# SWD_Adapter.net
KiCad netlist of a schematic drawn in Altium Designer
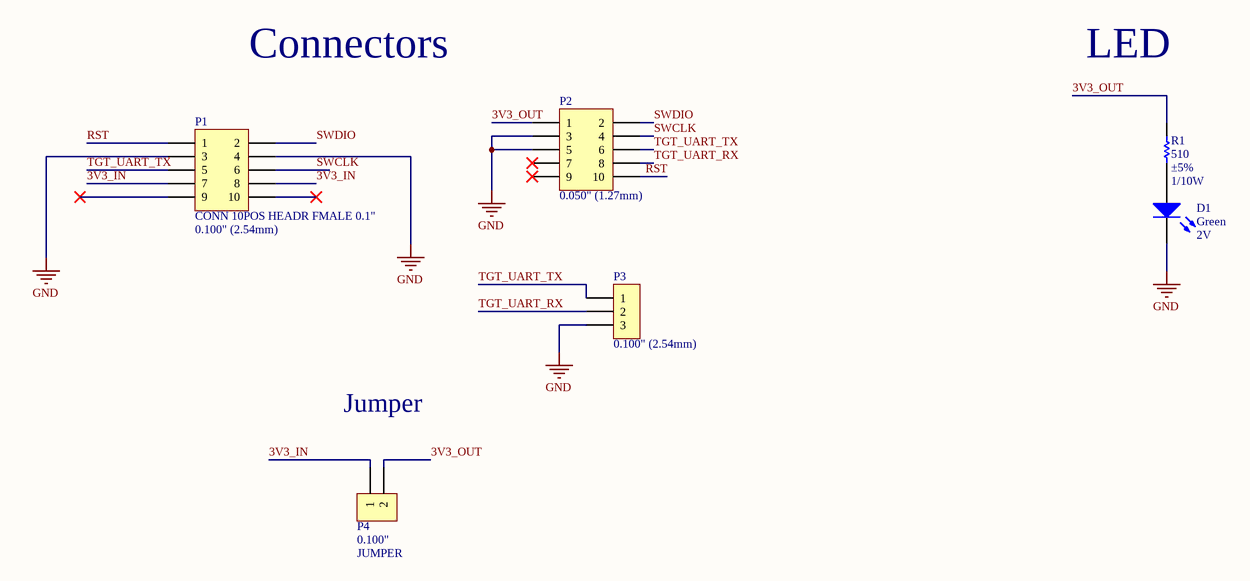
[diagram p0: SWD_Adapter.SchDoc]

(export (version "E")
  (design (tool "Eeschema 10.0.6"))
  (components
    (comp (ref "D1")
      (value "LED GREEN CLEAR 2V 0603")
      (footprint "LED_0603")
      (description "Green 572nm LED Indication - Discrete 2V 0603 (1608 Metric)")
      (fields
        (field (name "COLOR") "Green")
        (field (name "MANUFACTURER") "Wurth Electronics Inc.")
        (field (name "MANUFACTURER PART NUMBER") "150060VS75000")
        (field (name "VOLTAGE - FORWARD (VF) (TYP)") "2V")
      )
      (libsource (lib "Schematic Diagrams") (part "LED GREEN CLEAR 2V 0603"))
    )
    (comp (ref "P1")
      (value "CONN 10POS HEADR FMALE 0.1\"")
      (footprint "CONN ,10 POS Header 0.100\"")
      (description "10 Position Header Connector 0.100\" (2.54mm) Through Hole, Right Angle Gold")
      (fields (field (name "PITCH - MATING") "0.100\" (2.54mm)"))
      (libsource (lib "Schematic Diagrams") (part "CONN 10POS HEADR FMALE 0.1{dblquote}"))
    )
    (comp (ref "P2")
      (value "CONN 10POS HEADR MALE 0.05\"")
      (footprint "CONN, 10POS 0.05\" Debug Header")
      (description "10 Positions Header Connector 0.050\" (1.27mm) Surface Mount Gold")
      (fields (field (name "PITCH - MATING") "0.050\" (1.27mm)"))
      (libsource (lib "Schematic Diagrams") (part "CONN 10POS HEADR MALE 0.05{dblquote}"))
    )
    (comp (ref "P3")
      (value "CONN 3POS HEADR MALE 0.1\"")
      (description "3 Positions Header Connector 0.100\" (2.54mm) Through Hole Gold")
      (fields (field (name "VOLTAGE") "250V") (field (name "PITCH - MATING") "0.100\" (2.54mm)"))
      (libsource (lib "Schematic Diagrams") (part "CONN 3POS HEADR MALE 0.1{dblquote}"))
    )
    (comp (ref "P4")
      (value "JUMPER")
      (footprint "CONN 2POS JUMPER 0.1\"")
      (description "2 Positions Header Connector Through Hole Gold")
      (fields
        (field (name "MANUFACTURER") "Omron Electronics Inc-EMC Div")
        (field (name "MANUFACTURER PART NUMBER") "XG8T-0231")
        (field (name "ROW SPACING - MATING") "0.100\"")
        (field (name "TYPE") "JUMPER")
      )
      (libsource (lib "Schematic Diagrams") (part "CONN 2POS JUMPER 0.1{dblquote}"))
    )
    (comp (ref "R1")
      (value "RES 510 OHM 5% 1/10W 0603")
      (footprint "RES, 0603")
      (description "RES SMD 510 OHM 5% 1/10W 0603")
      (fields
        (field (name "RESISTANCE") "510")
        (field (name "TOLERANCE") "±5%")
        (field (name "POWER") "1/10W")
      )
      (libsource (lib "Schematic Diagrams") (part "RES 510 OHM 5% 1/10W 0603"))
    )
  )
  (nets
    (net (code "1") (name "/3V3_IN") (class "Default")
      (node (ref "P1") (pin "7") (pinfunction "7_7") (pintype "passive"))
      (node (ref "P1") (pin "8") (pinfunction "8_8") (pintype "passive"))
      (node (ref "P4") (pin "1") (pinfunction "1_1") (pintype "passive"))
    )
    (net (code "2") (name "/3V3_OUT") (class "Default")
      (node (ref "P2") (pin "1") (pinfunction "1_1") (pintype "passive"))
      (node (ref "P4") (pin "2") (pinfunction "2_2") (pintype "passive"))
      (node (ref "R1") (pin "1") (pinfunction "1_1") (pintype "passive"))
    )
    (net (code "3") (name "/RST") (class "Default")
      (node (ref "P1") (pin "1") (pinfunction "1_1") (pintype "passive"))
      (node (ref "P2") (pin "10") (pinfunction "10_10") (pintype "passive"))
    )
    (net (code "4") (name "/SWCLK") (class "Default")
      (node (ref "P1") (pin "6") (pinfunction "6_6") (pintype "passive"))
      (node (ref "P2") (pin "4") (pinfunction "4_4") (pintype "passive"))
    )
    (net (code "5") (name "/SWDIO") (class "Default")
      (node (ref "P1") (pin "2") (pinfunction "2_2") (pintype "passive"))
      (node (ref "P2") (pin "2") (pinfunction "2_2") (pintype "passive"))
    )
    (net (code "6") (name "/TGT_UART_RX") (class "Default")
      (node (ref "P2") (pin "8") (pinfunction "8_8") (pintype "passive"))
      (node (ref "P3") (pin "2") (pinfunction "2_2") (pintype "passive"))
    )
    (net (code "7") (name "/TGT_UART_TX") (class "Default")
      (node (ref "P1") (pin "5") (pinfunction "5_5") (pintype "passive"))
      (node (ref "P2") (pin "6") (pinfunction "6_6") (pintype "passive"))
      (node (ref "P3") (pin "1") (pinfunction "1_1") (pintype "passive"))
    )
    (net (code "8") (name "GND") (class "Default")
      (node (ref "D1") (pin "2") (pinfunction "K_2") (pintype "passive"))
      (node (ref "P1") (pin "3") (pinfunction "3_3") (pintype "passive"))
      (node (ref "P1") (pin "4") (pinfunction "4_4") (pintype "passive"))
      (node (ref "P2") (pin "3") (pinfunction "3_3") (pintype "passive"))
      (node (ref "P2") (pin "5") (pinfunction "5_5") (pintype "passive"))
      (node (ref "P3") (pin "3") (pinfunction "3_3") (pintype "passive"))
    )
    (net (code "9") (name "Net-(D1-A)") (class "Default")
      (node (ref "D1") (pin "1") (pinfunction "A_1") (pintype "passive"))
      (node (ref "R1") (pin "2") (pinfunction "2_2") (pintype "passive"))
    )
    (net (code "10") (name "unconnected-(P1-Pad9)") (class "Default")
      (node (ref "P1") (pin "9") (pinfunction "9_9") (pintype "passive+no_connect"))
    )
    (net (code "11") (name "unconnected-(P1-Pad10)") (class "Default")
      (node (ref "P1") (pin "10") (pinfunction "10_10") (pintype "passive+no_connect"))
    )
    (net (code "12") (name "unconnected-(P2-Pad7)") (class "Default")
      (node (ref "P2") (pin "7") (pinfunction "7_7") (pintype "passive+no_connect"))
    )
    (net (code "13") (name "unconnected-(P2-Pad9)") (class "Default")
      (node (ref "P2") (pin "9") (pinfunction "9_9") (pintype "passive+no_connect"))
    )
  )
)
